# esp8266-bme280-deepsleep.net
KiCad netlist of a schematic drawn in EAGLE
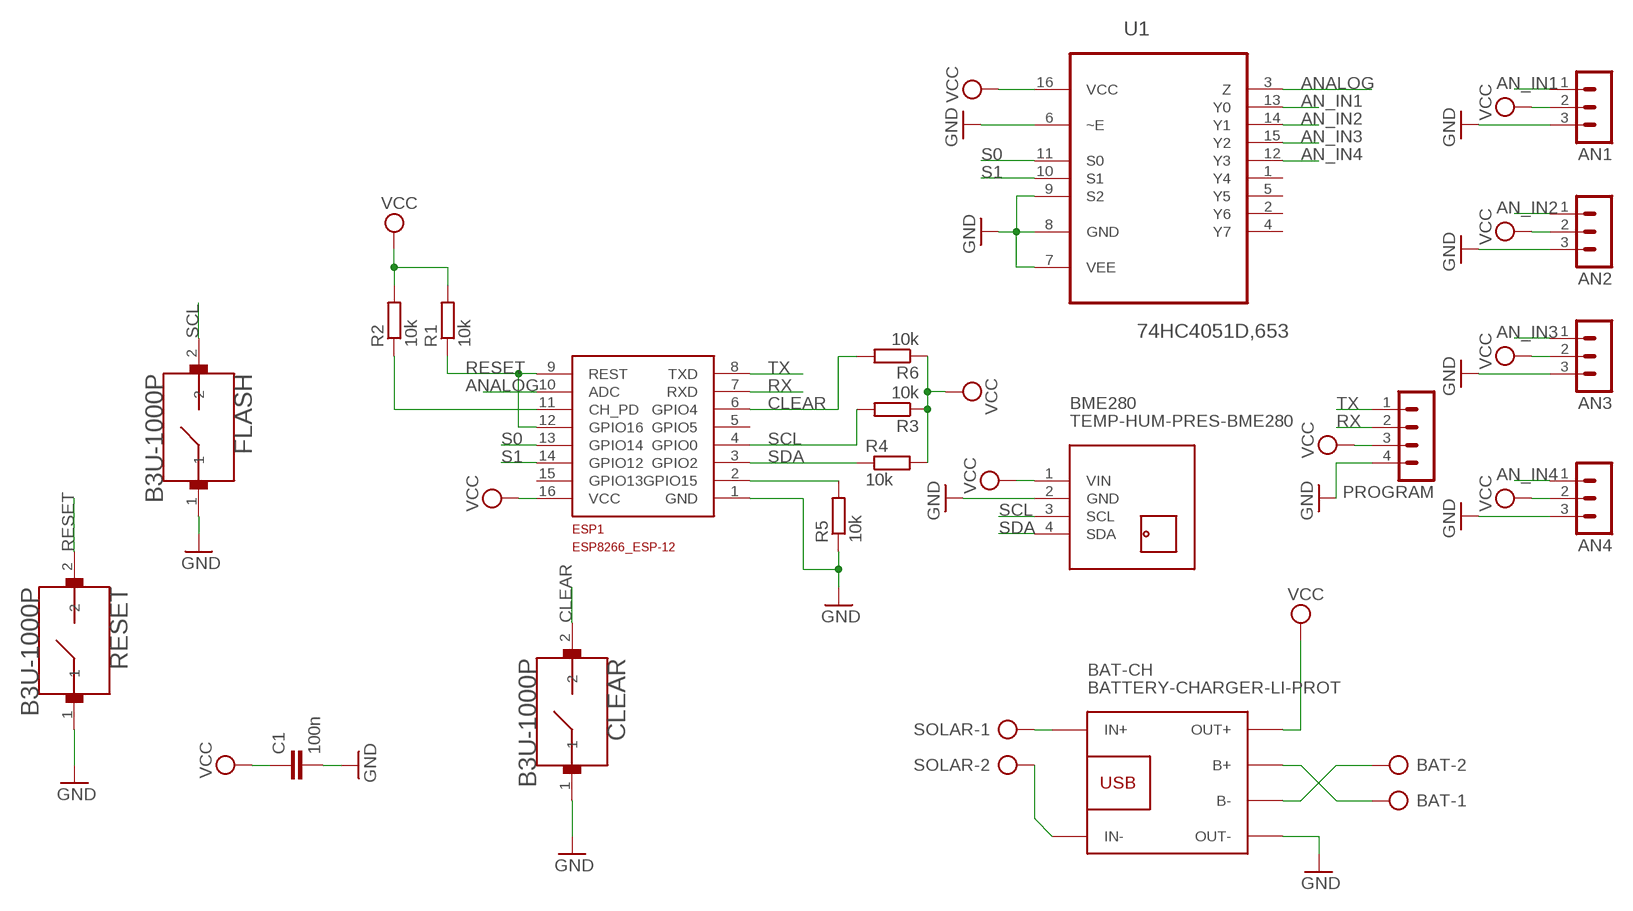
[diagram p0: schematic, sheet 1]

(export (version "E")
  (design (tool "Eeschema 10.0.6"))
  (components
    (comp (ref "AN1")
      (value "MA03-1")
      (footprint "eagle-import:MA03-1")
      (libsource (lib "eagle-import") (part "MA03-1"))
    )
    (comp (ref "AN2")
      (value "MA03-1")
      (footprint "eagle-import:MA03-1")
      (libsource (lib "eagle-import") (part "MA03-1"))
    )
    (comp (ref "AN3")
      (value "MA03-1")
      (footprint "eagle-import:MA03-1")
      (libsource (lib "eagle-import") (part "MA03-1"))
    )
    (comp (ref "AN4")
      (value "MA03-1")
      (footprint "eagle-import:MA03-1")
      (libsource (lib "eagle-import") (part "MA03-1"))
    )
    (comp (ref "BAT")
      (value "PWR_CONN_KK")
      (footprint "eagle-import:PWR_CONN_KK_5MM")
      (libsource (lib "eagle-import") (part "PWR_CONN_KK"))
    )
    (comp (ref "BAT-CH")
      (value "BATTERY-CHARGER-LI-PROT")
      (footprint "eagle-import:BATTERY-CHARGER-LI-PROT")
      (libsource (lib "eagle-import") (part "BATTERY-CHARGER-LI-PROT"))
    )
    (comp (ref "BME280")
      (value "TEMP-HUM-PRES-BME280")
      (footprint "eagle-import:TEMP-HUM-PRES-BME280")
      (libsource (lib "eagle-import") (part "TEMP-HUM-PRES-BME280"))
    )
    (comp (ref "C1")
      (value "100n")
      (footprint "eagle-import:C2.5-3")
      (libsource (lib "eagle-import") (part "C2,5-3"))
    )
    (comp (ref "CLEAR")
      (value "B3U-1000P")
      (footprint "eagle-import:SW_B3U-1000P")
      (fields (field (name "MF") "Omron"))
      (libsource (lib "eagle-import") (part "B3U-1000P"))
    )
    (comp (ref "ESP1")
      (value "ESP8266_ESP-12")
      (footprint "eagle-import:ESP8266-ESP12")
      (libsource (lib "eagle-import") (part "ESP8266_ESP-12"))
    )
    (comp (ref "FLASH")
      (value "B3U-1000P")
      (footprint "eagle-import:SW_B3U-1000P")
      (fields (field (name "MF") "Omron"))
      (libsource (lib "eagle-import") (part "B3U-1000P"))
    )
    (comp (ref "PROGRAM")
      (value "MA04-1")
      (footprint "eagle-import:MA04-1")
      (libsource (lib "eagle-import") (part "MA04-1"))
    )
    (comp (ref "R1")
      (value "10k")
      (footprint "eagle-import:0204_7")
      (libsource (lib "eagle-import") (part "R-EU_0204/7"))
    )
    (comp (ref "R2")
      (value "10k")
      (footprint "eagle-import:0204_7")
      (libsource (lib "eagle-import") (part "R-EU_0204/7"))
    )
    (comp (ref "R3")
      (value "10k")
      (footprint "eagle-import:0204_7")
      (libsource (lib "eagle-import") (part "R-EU_0204/7"))
    )
    (comp (ref "R4")
      (value "10k")
      (footprint "eagle-import:0204_7")
      (libsource (lib "eagle-import") (part "R-EU_0204/7"))
    )
    (comp (ref "R5")
      (value "10k")
      (footprint "eagle-import:0204_7")
      (libsource (lib "eagle-import") (part "R-EU_0204/7"))
    )
    (comp (ref "R6")
      (value "10k")
      (footprint "eagle-import:0204_7")
      (libsource (lib "eagle-import") (part "R-EU_0204/7"))
    )
    (comp (ref "RESET")
      (value "B3U-1000P")
      (footprint "eagle-import:SW_B3U-1000P")
      (fields (field (name "MF") "Omron"))
      (libsource (lib "eagle-import") (part "B3U-1000P"))
    )
    (comp (ref "SOLAR")
      (value "PWR_CONN_KK")
      (footprint "eagle-import:PWR_CONN_KK_5MM")
      (libsource (lib "eagle-import") (part "PWR_CONN_KK"))
    )
    (comp (ref "U1")
      (value "74HC4051D,653")
      (footprint "eagle-import:SOIC127P600X175-16N")
      (fields (field (name "MF") "Nexperia"))
      (libsource (lib "eagle-import") (part "74HC4051D,653"))
    )
  )
  (nets
    (net (code "1") (name "/ANALOG") (class "Default")
      (node (ref "ESP1") (pin "10") (pinfunction "ADC_10") (pintype "bidirectional"))
      (node (ref "U1") (pin "3") (pinfunction "Z_3") (pintype "bidirectional"))
    )
    (net (code "2") (name "/AN_IN1") (class "Default")
      (node (ref "AN1") (pin "1") (pinfunction "1_1") (pintype "passive"))
      (node (ref "U1") (pin "13") (pinfunction "Y0_13") (pintype "bidirectional"))
    )
    (net (code "3") (name "/AN_IN2") (class "Default")
      (node (ref "AN2") (pin "1") (pinfunction "1_1") (pintype "passive"))
      (node (ref "U1") (pin "14") (pinfunction "Y1_14") (pintype "bidirectional"))
    )
    (net (code "4") (name "/AN_IN3") (class "Default")
      (node (ref "AN3") (pin "1") (pinfunction "1_1") (pintype "passive"))
      (node (ref "U1") (pin "15") (pinfunction "Y2_15") (pintype "bidirectional"))
    )
    (net (code "5") (name "/AN_IN4") (class "Default")
      (node (ref "AN4") (pin "1") (pinfunction "1_1") (pintype "passive"))
      (node (ref "U1") (pin "12") (pinfunction "Y3_12") (pintype "bidirectional"))
    )
    (net (code "6") (name "/CLEAR") (class "Default")
      (node (ref "CLEAR") (pin "2") (pinfunction "2_2") (pintype "passive"))
      (node (ref "ESP1") (pin "6") (pinfunction "GPIO4_6") (pintype "bidirectional"))
      (node (ref "R6") (pin "2") (pinfunction "2_2") (pintype "passive"))
    )
    (net (code "7") (name "/RESET") (class "Default")
      (node (ref "ESP1") (pin "12") (pinfunction "GPIO16_12") (pintype "bidirectional"))
      (node (ref "ESP1") (pin "9") (pinfunction "REST_9") (pintype "bidirectional"))
      (node (ref "R1") (pin "1") (pinfunction "1_1") (pintype "passive"))
      (node (ref "RESET") (pin "2") (pinfunction "2_2") (pintype "passive"))
    )
    (net (code "8") (name "/RX") (class "Default")
      (node (ref "ESP1") (pin "7") (pinfunction "RXD_7") (pintype "bidirectional"))
      (node (ref "PROGRAM") (pin "2") (pinfunction "2_2") (pintype "passive"))
    )
    (net (code "9") (name "/S0") (class "Default")
      (node (ref "ESP1") (pin "13") (pinfunction "GPIO14_13") (pintype "bidirectional"))
      (node (ref "U1") (pin "11") (pinfunction "S0_11") (pintype "input"))
    )
    (net (code "10") (name "/S1") (class "Default")
      (node (ref "ESP1") (pin "14") (pinfunction "GPIO12_14") (pintype "bidirectional"))
      (node (ref "U1") (pin "10") (pinfunction "S1_10") (pintype "input"))
    )
    (net (code "11") (name "/SCL") (class "Default")
      (node (ref "BME280") (pin "3") (pinfunction "SCL_3") (pintype "bidirectional"))
      (node (ref "ESP1") (pin "4") (pinfunction "GPIO0_4") (pintype "bidirectional"))
      (node (ref "FLASH") (pin "2") (pinfunction "2_2") (pintype "passive"))
      (node (ref "R3") (pin "2") (pinfunction "2_2") (pintype "passive"))
    )
    (net (code "12") (name "/SDA") (class "Default")
      (node (ref "BME280") (pin "4") (pinfunction "SDA_4") (pintype "bidirectional"))
      (node (ref "ESP1") (pin "3") (pinfunction "GPIO2_3") (pintype "bidirectional"))
      (node (ref "R4") (pin "1") (pinfunction "1_1") (pintype "passive"))
    )
    (net (code "13") (name "/TX") (class "Default")
      (node (ref "ESP1") (pin "8") (pinfunction "TXD_8") (pintype "bidirectional"))
      (node (ref "PROGRAM") (pin "1") (pinfunction "1_1") (pintype "passive"))
    )
    (net (code "14") (name "GND") (class "Default")
      (node (ref "AN1") (pin "3") (pinfunction "3_3") (pintype "passive"))
      (node (ref "AN2") (pin "3") (pinfunction "3_3") (pintype "passive"))
      (node (ref "AN3") (pin "3") (pinfunction "3_3") (pintype "passive"))
      (node (ref "AN4") (pin "3") (pinfunction "3_3") (pintype "passive"))
      (node (ref "BAT-CH") (pin "OUT-") (pinfunction "OUT-_OUT-") (pintype "bidirectional"))
      (node (ref "BME280") (pin "2") (pinfunction "GND_2") (pintype "power_in"))
      (node (ref "C1") (pin "2") (pinfunction "2_2") (pintype "passive"))
      (node (ref "CLEAR") (pin "1") (pinfunction "1_1") (pintype "passive"))
      (node (ref "ESP1") (pin "1") (pinfunction "GND_1") (pintype "bidirectional"))
      (node (ref "FLASH") (pin "1") (pinfunction "1_1") (pintype "passive"))
      (node (ref "PROGRAM") (pin "4") (pinfunction "4_4") (pintype "passive"))
      (node (ref "R5") (pin "1") (pinfunction "1_1") (pintype "passive"))
      (node (ref "RESET") (pin "1") (pinfunction "1_1") (pintype "passive"))
      (node (ref "U1") (pin "6") (pinfunction "~{E}_6") (pintype "input"))
      (node (ref "U1") (pin "7") (pinfunction "VEE_7") (pintype "power_in"))
      (node (ref "U1") (pin "8") (pinfunction "GND_8") (pintype "passive"))
      (node (ref "U1") (pin "9") (pinfunction "S2_9") (pintype "input"))
    )
    (net (code "15") (name "Net-(BATA-KL)") (class "Default")
      (node (ref "BAT") (pin "1") (pinfunction "KL_1") (pintype "passive"))
      (node (ref "BAT-CH") (pin "B+") (pinfunction "B+_B+") (pintype "bidirectional"))
    )
    (net (code "16") (name "Net-(BATB-KL)") (class "Default")
      (node (ref "BAT") (pin "2") (pinfunction "KL_2") (pintype "passive"))
      (node (ref "BAT-CH") (pin "B-") (pinfunction "B-_B-") (pintype "bidirectional"))
    )
    (net (code "17") (name "Net-(ESP1-CH_PD)") (class "Default")
      (node (ref "ESP1") (pin "11") (pinfunction "CH_PD_11") (pintype "bidirectional"))
      (node (ref "R2") (pin "1") (pinfunction "1_1") (pintype "passive"))
    )
    (net (code "18") (name "Net-(ESP1-GPIO15)") (class "Default")
      (node (ref "ESP1") (pin "2") (pinfunction "GPIO15_2") (pintype "bidirectional"))
      (node (ref "R5") (pin "2") (pinfunction "2_2") (pintype "passive"))
    )
    (net (code "19") (name "Net-(SOLARA-KL)") (class "Default")
      (node (ref "BAT-CH") (pin "IN+") (pinfunction "IN+_IN+") (pintype "bidirectional"))
      (node (ref "SOLAR") (pin "1") (pinfunction "KL_1") (pintype "passive"))
    )
    (net (code "20") (name "Net-(SOLARB-KL)") (class "Default")
      (node (ref "BAT-CH") (pin "IN-") (pinfunction "IN-_IN-") (pintype "bidirectional"))
      (node (ref "SOLAR") (pin "2") (pinfunction "KL_2") (pintype "passive"))
    )
    (net (code "21") (name "VCC") (class "Default")
      (node (ref "AN1") (pin "2") (pinfunction "2_2") (pintype "passive"))
      (node (ref "AN2") (pin "2") (pinfunction "2_2") (pintype "passive"))
      (node (ref "AN3") (pin "2") (pinfunction "2_2") (pintype "passive"))
      (node (ref "AN4") (pin "2") (pinfunction "2_2") (pintype "passive"))
      (node (ref "BAT-CH") (pin "OUT+") (pinfunction "OUT+_OUT+") (pintype "bidirectional"))
      (node (ref "BME280") (pin "1") (pinfunction "VIN_1") (pintype "power_in"))
      (node (ref "C1") (pin "1") (pinfunction "1_1") (pintype "passive"))
      (node (ref "ESP1") (pin "16") (pinfunction "VCC_16") (pintype "bidirectional"))
      (node (ref "PROGRAM") (pin "3") (pinfunction "3_3") (pintype "passive"))
      (node (ref "R1") (pin "2") (pinfunction "2_2") (pintype "passive"))
      (node (ref "R2") (pin "2") (pinfunction "2_2") (pintype "passive"))
      (node (ref "R3") (pin "1") (pinfunction "1_1") (pintype "passive"))
      (node (ref "R4") (pin "2") (pinfunction "2_2") (pintype "passive"))
      (node (ref "R6") (pin "1") (pinfunction "1_1") (pintype "passive"))
      (node (ref "U1") (pin "16") (pinfunction "VCC_16") (pintype "power_in"))
    )
    (net (code "22") (name "unconnected-(ESP1-GPIO5-Pad5)") (class "Default")
      (node (ref "ESP1") (pin "5") (pinfunction "GPIO5_5") (pintype "bidirectional"))
    )
    (net (code "23") (name "unconnected-(ESP1-GPIO13-Pad15)") (class "Default")
      (node (ref "ESP1") (pin "15") (pinfunction "GPIO13_15") (pintype "bidirectional"))
    )
    (net (code "24") (name "unconnected-(U1-Y4-Pad1)") (class "Default")
      (node (ref "U1") (pin "1") (pinfunction "Y4_1") (pintype "bidirectional"))
    )
    (net (code "25") (name "unconnected-(U1-Y5-Pad5)") (class "Default")
      (node (ref "U1") (pin "5") (pinfunction "Y5_5") (pintype "bidirectional"))
    )
    (net (code "26") (name "unconnected-(U1-Y6-Pad2)") (class "Default")
      (node (ref "U1") (pin "2") (pinfunction "Y6_2") (pintype "bidirectional"))
    )
    (net (code "27") (name "unconnected-(U1-Y7-Pad4)") (class "Default")
      (node (ref "U1") (pin "4") (pinfunction "Y7_4") (pintype "bidirectional"))
    )
  )
)
